# DummyLoad.net
KiCad netlist of a schematic drawn in EAGLE
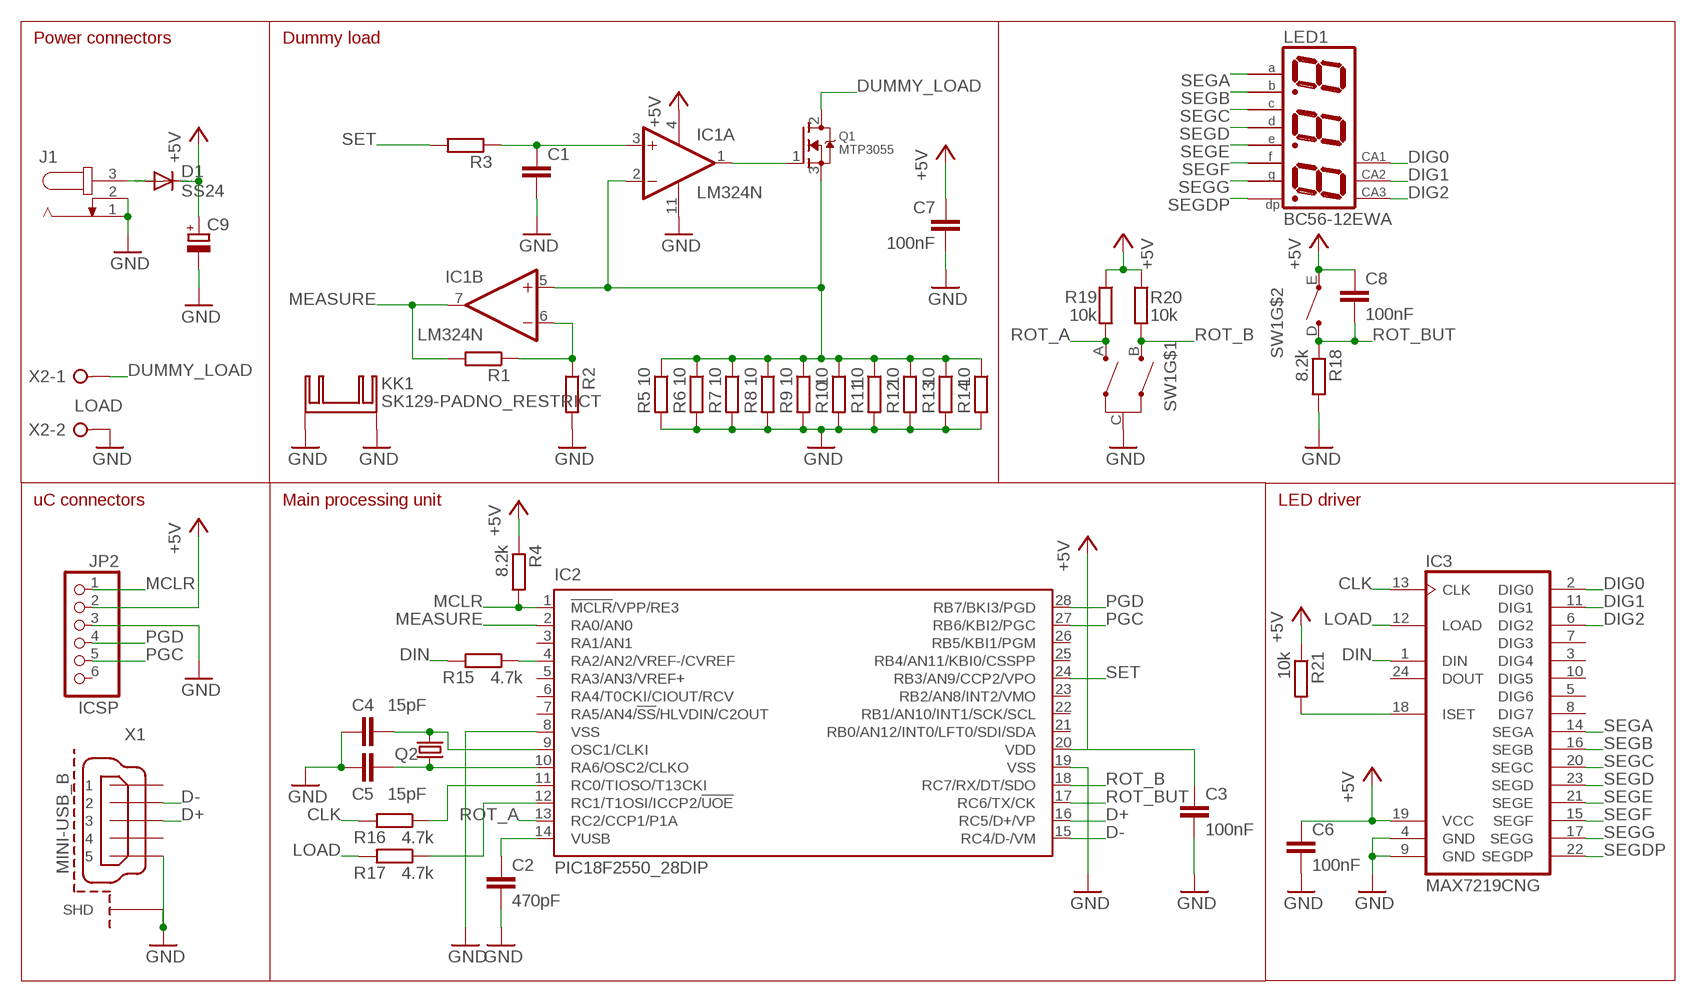
[diagram p0: schematic, sheet 1]

(export (version "E")
  (design (tool "Eeschema 10.0.6"))
  (components
    (comp (ref "C1")
      (value "C-EUC1206")
      (footprint "eagle-import:C1206")
      (libsource (lib "eagle-import") (part "C-EUC1206"))
    )
    (comp (ref "C2")
      (value "470pF")
      (footprint "eagle-import:C1206")
      (libsource (lib "eagle-import") (part "C-EUC1206"))
    )
    (comp (ref "C3")
      (value "100nF")
      (footprint "eagle-import:C1206")
      (libsource (lib "eagle-import") (part "C-EUC1206"))
    )
    (comp (ref "C4")
      (value "15pF")
      (footprint "eagle-import:C1206")
      (libsource (lib "eagle-import") (part "C-EUC1206"))
    )
    (comp (ref "C5")
      (value "15pF")
      (footprint "eagle-import:C1206")
      (libsource (lib "eagle-import") (part "C-EUC1206"))
    )
    (comp (ref "C6")
      (value "100nF")
      (footprint "eagle-import:C1206")
      (libsource (lib "eagle-import") (part "C-EUC1206"))
    )
    (comp (ref "C7")
      (value "100nF")
      (footprint "eagle-import:C1206")
      (libsource (lib "eagle-import") (part "C-EUC1206"))
    )
    (comp (ref "C8")
      (value "100nF")
      (footprint "eagle-import:C1206")
      (libsource (lib "eagle-import") (part "C-EUC1206"))
    )
    (comp (ref "C9")
      (value "CPOL-EUD/7343-31R")
      (footprint "eagle-import:D_7343-31R")
      (libsource (lib "eagle-import") (part "CPOL-EUD/7343-31R"))
    )
    (comp (ref "D1")
      (value "SS24")
      (footprint "eagle-import:DO214AA")
      (libsource (lib "eagle-import") (part "DIODE-DO214AA"))
    )
    (comp (ref "IC1")
      (value "LM324N")
      (footprint "eagle-import:DIL14")
      (libsource (lib "eagle-import") (part "LM324N"))
    )
    (comp (ref "IC2")
      (value "PIC18F2550_28DIP")
      (footprint "eagle-import:DIL28-3")
      (fields (field (name "MF") "MICROCHIP") (field (name "MPN") "PIC18F2550-I/SP"))
      (libsource (lib "eagle-import") (part "PIC18F2_28DIP550"))
    )
    (comp (ref "IC3")
      (value "MAX7219CNG")
      (footprint "eagle-import:DIL24-3")
      (fields (field (name "MF") "MAXIM"))
      (libsource (lib "eagle-import") (part "MAX7219CNG"))
    )
    (comp (ref "J1")
      (value "JACK-PLUG0")
      (footprint "eagle-import:SPC4077")
      (libsource (lib "eagle-import") (part "JACK-PLUG0"))
    )
    (comp (ref "JP2")
      (value "ICSP")
      (footprint "eagle-import:1X06_90")
      (libsource (lib "eagle-import") (part "PINHD-1X6/90"))
    )
    (comp (ref "KK1")
      (value "SK129-PADNO_RESTRICT")
      (footprint "eagle-import:SK129-NO_RESTRICT")
      (libsource (lib "eagle-import") (part "SK129-PADNO_RESTRICT"))
    )
    (comp (ref "LED1")
      (value "BC56-12EWA")
      (footprint "eagle-import:BX56-12")
      (libsource (lib "eagle-import") (part "B?56-12WACE"))
    )
    (comp (ref "Q1")
      (value "MTP3055")
      (footprint "eagle-import:TO220V")
      (libsource (lib "eagle-import") (part "MOSFET-NGDS_TO220V"))
    )
    (comp (ref "Q2")
      (value "CRYSTALHC49S")
      (footprint "eagle-import:HC49_S")
      (libsource (lib "eagle-import") (part "CRYSTALHC49S"))
    )
    (comp (ref "R1")
      (value "R-EU_R1206")
      (footprint "eagle-import:R1206")
      (libsource (lib "eagle-import") (part "R-EU_R1206"))
    )
    (comp (ref "R2")
      (value "R-EU_R1206")
      (footprint "eagle-import:R1206")
      (libsource (lib "eagle-import") (part "R-EU_R1206"))
    )
    (comp (ref "R3")
      (value "R-EU_R1206")
      (footprint "eagle-import:R1206")
      (libsource (lib "eagle-import") (part "R-EU_R1206"))
    )
    (comp (ref "R4")
      (value "8.2k")
      (footprint "eagle-import:R1206")
      (libsource (lib "eagle-import") (part "R-EU_R1206"))
    )
    (comp (ref "R5")
      (value "10")
      (footprint "eagle-import:0309_12")
      (libsource (lib "eagle-import") (part "R-EU_0309/12"))
    )
    (comp (ref "R6")
      (value "10")
      (footprint "eagle-import:0309_12")
      (libsource (lib "eagle-import") (part "R-EU_0309/12"))
    )
    (comp (ref "R7")
      (value "10")
      (footprint "eagle-import:0309_12")
      (libsource (lib "eagle-import") (part "R-EU_0309/12"))
    )
    (comp (ref "R8")
      (value "10")
      (footprint "eagle-import:0309_12")
      (libsource (lib "eagle-import") (part "R-EU_0309/12"))
    )
    (comp (ref "R9")
      (value "10")
      (footprint "eagle-import:0309_12")
      (libsource (lib "eagle-import") (part "R-EU_0309/12"))
    )
    (comp (ref "R10")
      (value "10")
      (footprint "eagle-import:0309_12")
      (libsource (lib "eagle-import") (part "R-EU_0309/12"))
    )
    (comp (ref "R11")
      (value "10")
      (footprint "eagle-import:0309_12")
      (libsource (lib "eagle-import") (part "R-EU_0309/12"))
    )
    (comp (ref "R12")
      (value "10")
      (footprint "eagle-import:0309_12")
      (libsource (lib "eagle-import") (part "R-EU_0309/12"))
    )
    (comp (ref "R13")
      (value "10")
      (footprint "eagle-import:0309_12")
      (libsource (lib "eagle-import") (part "R-EU_0309/12"))
    )
    (comp (ref "R14")
      (value "10")
      (footprint "eagle-import:0309_12")
      (libsource (lib "eagle-import") (part "R-EU_0309/12"))
    )
    (comp (ref "R15")
      (value "4.7k")
      (footprint "eagle-import:R1206")
      (libsource (lib "eagle-import") (part "R-EU_R1206"))
    )
    (comp (ref "R16")
      (value "4.7k")
      (footprint "eagle-import:R1206")
      (libsource (lib "eagle-import") (part "R-EU_R1206"))
    )
    (comp (ref "R17")
      (value "4.7k")
      (footprint "eagle-import:R1206")
      (libsource (lib "eagle-import") (part "R-EU_R1206"))
    )
    (comp (ref "R18")
      (value "8.2k")
      (footprint "eagle-import:R1206")
      (libsource (lib "eagle-import") (part "R-EU_R1206"))
    )
    (comp (ref "R19")
      (value "10k")
      (footprint "eagle-import:R1206")
      (libsource (lib "eagle-import") (part "R-EU_R1206"))
    )
    (comp (ref "R20")
      (value "10k")
      (footprint "eagle-import:R1206")
      (libsource (lib "eagle-import") (part "R-EU_R1206"))
    )
    (comp (ref "R21")
      (value "10k")
      (footprint "eagle-import:R1206")
      (libsource (lib "eagle-import") (part "R-EU_R1206"))
    )
    (comp (ref "SW1")
      (value "EC11B-V-T")
      (footprint "eagle-import:EC11B-V")
      (libsource (lib "eagle-import") (part "EC11B-V-T"))
    )
    (comp (ref "X1")
      (value "MINI-USB_B")
      (footprint "eagle-import:MINI-USB-B")
      (libsource (lib "eagle-import") (part "MINI-USB_B"))
    )
    (comp (ref "X2")
      (value "LOAD")
      (footprint "eagle-import:W237-132")
      (libsource (lib "eagle-import") (part "W237-02P"))
    )
  )
  (nets
    (net (code "1") (name "+5V") (class "Default")
      (node (ref "C3") (pin "1") (pinfunction "1_1") (pintype "passive"))
      (node (ref "C6") (pin "1") (pinfunction "1_1") (pintype "passive"))
      (node (ref "C7") (pin "1") (pinfunction "1_1") (pintype "passive"))
      (node (ref "C8") (pin "1") (pinfunction "1_1") (pintype "passive"))
      (node (ref "C9") (pin "+") (pinfunction "+_+") (pintype "passive"))
      (node (ref "D1") (pin "C") (pinfunction "C_C") (pintype "passive"))
      (node (ref "IC1") (pin "4") (pinfunction "V+_4") (pintype "power_in"))
      (node (ref "IC2") (pin "20") (pinfunction "VDD_20") (pintype "power_in"))
      (node (ref "IC3") (pin "19") (pinfunction "VCC_19") (pintype "power_in"))
      (node (ref "JP2") (pin "2") (pinfunction "2_2") (pintype "passive"))
      (node (ref "R19") (pin "1") (pinfunction "1_1") (pintype "passive"))
      (node (ref "R20") (pin "1") (pinfunction "1_1") (pintype "passive"))
      (node (ref "R21") (pin "1") (pinfunction "1_1") (pintype "passive"))
      (node (ref "R4") (pin "1") (pinfunction "1_1") (pintype "passive"))
      (node (ref "SW1") (pin "E") (pinfunction "E_E") (pintype "passive"))
    )
    (net (code "2") (name "/CLK") (class "Default")
      (node (ref "IC3") (pin "13") (pinfunction "CLK_13") (pintype "input"))
      (node (ref "R16") (pin "2") (pinfunction "2_2") (pintype "passive"))
    )
    (net (code "3") (name "/D+") (class "Default")
      (node (ref "IC2") (pin "16") (pinfunction "RC5/D+/VP_16") (pintype "bidirectional"))
      (node (ref "X1") (pin "3") (pinfunction "3_3") (pintype "passive"))
    )
    (net (code "4") (name "/D-") (class "Default")
      (node (ref "IC2") (pin "15") (pinfunction "RC4/D-/VM_15") (pintype "bidirectional"))
      (node (ref "X1") (pin "2") (pinfunction "2_2") (pintype "passive"))
    )
    (net (code "5") (name "/DIG0") (class "Default")
      (node (ref "IC3") (pin "2") (pinfunction "DIG0_2") (pintype "output"))
      (node (ref "LED1") (pin "12") (pinfunction "CA_12") (pintype "passive"))
    )
    (net (code "6") (name "/DIG1") (class "Default")
      (node (ref "IC3") (pin "11") (pinfunction "DIG1_11") (pintype "output"))
      (node (ref "LED1") (pin "9") (pinfunction "CA_9") (pintype "passive"))
    )
    (net (code "7") (name "/DIG2") (class "Default")
      (node (ref "IC3") (pin "6") (pinfunction "DIG2_6") (pintype "output"))
      (node (ref "LED1") (pin "8") (pinfunction "CA_8") (pintype "passive"))
    )
    (net (code "8") (name "/DIN") (class "Default")
      (node (ref "IC3") (pin "1") (pinfunction "DIN_1") (pintype "input"))
      (node (ref "R15") (pin "2") (pinfunction "2_2") (pintype "passive"))
    )
    (net (code "9") (name "/DUMMY_LOAD") (class "Default")
      (node (ref "Q1") (pin "2") (pinfunction "D_2") (pintype "bidirectional"))
      (node (ref "X2") (pin "1") (pinfunction "KL_1") (pintype "passive"))
    )
    (net (code "10") (name "/LOAD") (class "Default")
      (node (ref "IC3") (pin "12") (pinfunction "LOAD_12") (pintype "input"))
      (node (ref "R17") (pin "2") (pinfunction "2_2") (pintype "passive"))
    )
    (net (code "11") (name "/MCLR") (class "Default")
      (node (ref "IC2") (pin "1") (pinfunction "~{MCLR}/VPP/RE3_1") (pintype "input"))
      (node (ref "JP2") (pin "1") (pinfunction "1_1") (pintype "passive"))
      (node (ref "R4") (pin "2") (pinfunction "2_2") (pintype "passive"))
    )
    (net (code "12") (name "/MEASURE") (class "Default")
      (node (ref "IC1") (pin "7") (pinfunction "OUT_7") (pintype "output"))
      (node (ref "IC2") (pin "2") (pinfunction "RA0/AN0_2") (pintype "bidirectional"))
      (node (ref "R1") (pin "2") (pinfunction "2_2") (pintype "passive"))
    )
    (net (code "13") (name "/PGC") (class "Default")
      (node (ref "IC2") (pin "27") (pinfunction "RB6/KBI2/PGC_27") (pintype "bidirectional"))
      (node (ref "JP2") (pin "5") (pinfunction "5_5") (pintype "passive"))
    )
    (net (code "14") (name "/PGD") (class "Default")
      (node (ref "IC2") (pin "28") (pinfunction "RB7/BKI3/PGD_28") (pintype "bidirectional"))
      (node (ref "JP2") (pin "4") (pinfunction "4_4") (pintype "passive"))
    )
    (net (code "15") (name "/ROT_A") (class "Default")
      (node (ref "IC2") (pin "13") (pinfunction "RC2/CCP1/P1A_13") (pintype "bidirectional"))
      (node (ref "R19") (pin "2") (pinfunction "2_2") (pintype "passive"))
      (node (ref "SW1") (pin "A") (pinfunction "A_A") (pintype "passive"))
    )
    (net (code "16") (name "/ROT_B") (class "Default")
      (node (ref "IC2") (pin "18") (pinfunction "RC7/RX/DT/SDO_18") (pintype "bidirectional"))
      (node (ref "R20") (pin "2") (pinfunction "2_2") (pintype "passive"))
      (node (ref "SW1") (pin "B") (pinfunction "B_B") (pintype "passive"))
    )
    (net (code "17") (name "/ROT_BUT") (class "Default")
      (node (ref "C8") (pin "2") (pinfunction "2_2") (pintype "passive"))
      (node (ref "IC2") (pin "17") (pinfunction "RC6/TX/CK_17") (pintype "bidirectional"))
      (node (ref "R18") (pin "1") (pinfunction "1_1") (pintype "passive"))
      (node (ref "SW1") (pin "D") (pinfunction "D_D") (pintype "passive"))
    )
    (net (code "18") (name "/SEGA") (class "Default")
      (node (ref "IC3") (pin "14") (pinfunction "SEGA_14") (pintype "output"))
      (node (ref "LED1") (pin "11") (pinfunction "A_11") (pintype "passive"))
    )
    (net (code "19") (name "/SEGB") (class "Default")
      (node (ref "IC3") (pin "16") (pinfunction "SEGB_16") (pintype "output"))
      (node (ref "LED1") (pin "7") (pinfunction "B_7") (pintype "passive"))
    )
    (net (code "20") (name "/SEGC") (class "Default")
      (node (ref "IC3") (pin "20") (pinfunction "SEGC_20") (pintype "output"))
      (node (ref "LED1") (pin "4") (pinfunction "C_4") (pintype "passive"))
    )
    (net (code "21") (name "/SEGD") (class "Default")
      (node (ref "IC3") (pin "23") (pinfunction "SEGD_23") (pintype "output"))
      (node (ref "LED1") (pin "2") (pinfunction "D_2") (pintype "passive"))
    )
    (net (code "22") (name "/SEGDP") (class "Default")
      (node (ref "IC3") (pin "22") (pinfunction "SEGDP_22") (pintype "output"))
      (node (ref "LED1") (pin "3") (pinfunction "DP_3") (pintype "passive"))
    )
    (net (code "23") (name "/SEGE") (class "Default")
      (node (ref "IC3") (pin "21") (pinfunction "SEGE_21") (pintype "output"))
      (node (ref "LED1") (pin "1") (pinfunction "E_1") (pintype "passive"))
    )
    (net (code "24") (name "/SEGF") (class "Default")
      (node (ref "IC3") (pin "15") (pinfunction "SEGF_15") (pintype "output"))
      (node (ref "LED1") (pin "10") (pinfunction "F_10") (pintype "passive"))
    )
    (net (code "25") (name "/SEGG") (class "Default")
      (node (ref "IC3") (pin "17") (pinfunction "SEGG_17") (pintype "output"))
      (node (ref "LED1") (pin "5") (pinfunction "G_5") (pintype "passive"))
    )
    (net (code "26") (name "/SET") (class "Default")
      (node (ref "IC2") (pin "24") (pinfunction "RB3/AN9/CCP2/VPO_24") (pintype "bidirectional"))
      (node (ref "R3") (pin "2") (pinfunction "2_2") (pintype "passive"))
    )
    (net (code "27") (name "GND") (class "Default")
      (node (ref "C1") (pin "2") (pinfunction "2_2") (pintype "passive"))
      (node (ref "C2") (pin "2") (pinfunction "2_2") (pintype "passive"))
      (node (ref "C3") (pin "2") (pinfunction "2_2") (pintype "passive"))
      (node (ref "C4") (pin "1") (pinfunction "1_1") (pintype "passive"))
      (node (ref "C5") (pin "1") (pinfunction "1_1") (pintype "passive"))
      (node (ref "C6") (pin "2") (pinfunction "2_2") (pintype "passive"))
      (node (ref "C7") (pin "2") (pinfunction "2_2") (pintype "passive"))
      (node (ref "C9") (pin "-") (pinfunction "-_-") (pintype "passive"))
      (node (ref "IC1") (pin "11") (pinfunction "V-_11") (pintype "power_in"))
      (node (ref "IC2") (pin "19") (pinfunction "VSS_19") (pintype "power_in"))
      (node (ref "IC2") (pin "8") (pinfunction "VSS_8") (pintype "power_in"))
      (node (ref "IC3") (pin "4") (pinfunction "GND_4") (pintype "power_in"))
      (node (ref "IC3") (pin "9") (pinfunction "GND_9") (pintype "power_in"))
      (node (ref "J1") (pin "1") (pinfunction "1_1") (pintype "passive"))
      (node (ref "J1") (pin "2") (pinfunction "2_2") (pintype "passive"))
      (node (ref "JP2") (pin "3") (pinfunction "3_3") (pintype "passive"))
      (node (ref "KK1") (pin "A2,5") (pinfunction "K_A2,5") (pintype "passive"))
      (node (ref "KK1") (pin "B2,5") (pinfunction "K_B2,5") (pintype "passive"))
      (node (ref "R10") (pin "2") (pinfunction "2_2") (pintype "passive"))
      (node (ref "R11") (pin "2") (pinfunction "2_2") (pintype "passive"))
      (node (ref "R12") (pin "2") (pinfunction "2_2") (pintype "passive"))
      (node (ref "R13") (pin "2") (pinfunction "2_2") (pintype "passive"))
      (node (ref "R14") (pin "2") (pinfunction "2_2") (pintype "passive"))
      (node (ref "R18") (pin "2") (pinfunction "2_2") (pintype "passive"))
      (node (ref "R2") (pin "2") (pinfunction "2_2") (pintype "passive"))
      (node (ref "R5") (pin "2") (pinfunction "2_2") (pintype "passive"))
      (node (ref "R6") (pin "2") (pinfunction "2_2") (pintype "passive"))
      (node (ref "R7") (pin "2") (pinfunction "2_2") (pintype "passive"))
      (node (ref "R8") (pin "2") (pinfunction "2_2") (pintype "passive"))
      (node (ref "R9") (pin "2") (pinfunction "2_2") (pintype "passive"))
      (node (ref "SW1") (pin "C") (pinfunction "C_C") (pintype "passive"))
      (node (ref "X1") (pin "5") (pinfunction "5_5") (pintype "passive"))
      (node (ref "X1") (pin "M1") (pinfunction "SHD_M1") (pintype "passive"))
      (node (ref "X1") (pin "M2") (pinfunction "SHD_M2") (pintype "passive"))
      (node (ref "X1") (pin "M3") (pinfunction "SHD_M3") (pintype "passive"))
      (node (ref "X1") (pin "M4") (pinfunction "SHD_M4") (pintype "passive"))
      (node (ref "X2") (pin "2") (pinfunction "KL_2") (pintype "passive"))
    )
    (net (code "28") (name "Net-(D1-PadA)") (class "Default")
      (node (ref "D1") (pin "A") (pinfunction "A_A") (pintype "passive"))
      (node (ref "J1") (pin "3") (pinfunction "3_3") (pintype "passive"))
    )
    (net (code "29") (name "Net-(IC1A-+IN)") (class "Default")
      (node (ref "C1") (pin "1") (pinfunction "1_1") (pintype "passive"))
      (node (ref "IC1") (pin "3") (pinfunction "+IN_3") (pintype "input"))
      (node (ref "R3") (pin "1") (pinfunction "1_1") (pintype "passive"))
    )
    (net (code "30") (name "Net-(IC1A--IN)") (class "Default")
      (node (ref "IC1") (pin "2") (pinfunction "-IN_2") (pintype "input"))
      (node (ref "IC1") (pin "5") (pinfunction "+IN_5") (pintype "input"))
      (node (ref "Q1") (pin "3") (pinfunction "S_3") (pintype "bidirectional"))
      (node (ref "R10") (pin "1") (pinfunction "1_1") (pintype "passive"))
      (node (ref "R11") (pin "1") (pinfunction "1_1") (pintype "passive"))
      (node (ref "R12") (pin "1") (pinfunction "1_1") (pintype "passive"))
      (node (ref "R13") (pin "1") (pinfunction "1_1") (pintype "passive"))
      (node (ref "R14") (pin "1") (pinfunction "1_1") (pintype "passive"))
      (node (ref "R5") (pin "1") (pinfunction "1_1") (pintype "passive"))
      (node (ref "R6") (pin "1") (pinfunction "1_1") (pintype "passive"))
      (node (ref "R7") (pin "1") (pinfunction "1_1") (pintype "passive"))
      (node (ref "R8") (pin "1") (pinfunction "1_1") (pintype "passive"))
      (node (ref "R9") (pin "1") (pinfunction "1_1") (pintype "passive"))
    )
    (net (code "31") (name "Net-(IC1A-OUT)") (class "Default")
      (node (ref "IC1") (pin "1") (pinfunction "OUT_1") (pintype "output"))
      (node (ref "Q1") (pin "1") (pinfunction "G_1") (pintype "bidirectional"))
    )
    (net (code "32") (name "Net-(IC1B--IN)") (class "Default")
      (node (ref "IC1") (pin "6") (pinfunction "-IN_6") (pintype "input"))
      (node (ref "R1") (pin "1") (pinfunction "1_1") (pintype "passive"))
      (node (ref "R2") (pin "1") (pinfunction "1_1") (pintype "passive"))
    )
    (net (code "33") (name "Net-(IC2-OSC1{slash}CLKI)") (class "Default")
      (node (ref "C4") (pin "2") (pinfunction "2_2") (pintype "passive"))
      (node (ref "IC2") (pin "9") (pinfunction "OSC1/CLKI_9") (pintype "input"))
      (node (ref "Q2") (pin "2") (pinfunction "2_2") (pintype "passive"))
    )
    (net (code "34") (name "Net-(IC2-RA2{slash}AN2{slash}VREF-{slash}CVREF)") (class "Default")
      (node (ref "IC2") (pin "4") (pinfunction "RA2/AN2/VREF-/CVREF_4") (pintype "bidirectional"))
      (node (ref "R15") (pin "1") (pinfunction "1_1") (pintype "passive"))
    )
    (net (code "35") (name "Net-(IC2-RA6{slash}OSC2{slash}CLKO)") (class "Default")
      (node (ref "C5") (pin "2") (pinfunction "2_2") (pintype "passive"))
      (node (ref "IC2") (pin "10") (pinfunction "RA6/OSC2/CLKO_10") (pintype "output"))
      (node (ref "Q2") (pin "1") (pinfunction "1_1") (pintype "passive"))
    )
    (net (code "36") (name "Net-(IC2-RC0{slash}TIOSO{slash}T13CKI)") (class "Default")
      (node (ref "IC2") (pin "11") (pinfunction "RC0/TIOSO/T13CKI_11") (pintype "bidirectional"))
      (node (ref "R16") (pin "1") (pinfunction "1_1") (pintype "passive"))
    )
    (net (code "37") (name "Net-(IC2-RC1{slash}T1OSI{slash}ICCP2{slash}~{UOE})") (class "Default")
      (node (ref "IC2") (pin "12") (pinfunction "RC1/T1OSI/ICCP2/~{UOE}_12") (pintype "bidirectional"))
      (node (ref "R17") (pin "1") (pinfunction "1_1") (pintype "passive"))
    )
    (net (code "38") (name "Net-(IC2-VUSB)") (class "Default")
      (node (ref "C2") (pin "1") (pinfunction "1_1") (pintype "passive"))
      (node (ref "IC2") (pin "14") (pinfunction "VUSB_14") (pintype "bidirectional"))
    )
    (net (code "39") (name "Net-(IC3-ISET)") (class "Default")
      (node (ref "IC3") (pin "18") (pinfunction "ISET_18") (pintype "input"))
      (node (ref "R21") (pin "2") (pinfunction "2_2") (pintype "passive"))
    )
    (net (code "40") (name "unconnected-(IC2-RA1{slash}AN1-Pad3)") (class "Default")
      (node (ref "IC2") (pin "3") (pinfunction "RA1/AN1_3") (pintype "bidirectional"))
    )
    (net (code "41") (name "unconnected-(IC2-RA3{slash}AN3{slash}VREF+-Pad5)") (class "Default")
      (node (ref "IC2") (pin "5") (pinfunction "RA3/AN3/VREF+_5") (pintype "bidirectional"))
    )
    (net (code "42") (name "unconnected-(IC2-RA4{slash}T0CKI{slash}CIOUT{slash}RCV-Pad6)") (class "Default")
      (node (ref "IC2") (pin "6") (pinfunction "RA4/T0CKI/CIOUT/RCV_6") (pintype "bidirectional"))
    )
    (net (code "43") (name "unconnected-(IC2-RA5{slash}AN4{slash}~{SS}{slash}HLVDIN{slash}C2OUT-Pad7)") (class "Default")
      (node (ref "IC2") (pin "7") (pinfunction "RA5/AN4/~{SS}/HLVDIN/C2OUT_7") (pintype "bidirectional"))
    )
    (net (code "44") (name "unconnected-(IC2-RB0{slash}AN12{slash}INT0{slash}LFT0{slash}SDI{slash}SDA-Pad21)") (class "Default")
      (node (ref "IC2") (pin "21") (pinfunction "RB0/AN12/INT0/LFT0/SDI/SDA_21") (pintype "bidirectional"))
    )
    (net (code "45") (name "unconnected-(IC2-RB1{slash}AN10{slash}INT1{slash}SCK{slash}SCL-Pad22)") (class "Default")
      (node (ref "IC2") (pin "22") (pinfunction "RB1/AN10/INT1/SCK/SCL_22") (pintype "bidirectional"))
    )
    (net (code "46") (name "unconnected-(IC2-RB2{slash}AN8{slash}INT2{slash}VMO-Pad23)") (class "Default")
      (node (ref "IC2") (pin "23") (pinfunction "RB2/AN8/INT2/VMO_23") (pintype "bidirectional"))
    )
    (net (code "47") (name "unconnected-(IC2-RB4{slash}AN11{slash}KBI0{slash}CSSPP-Pad25)") (class "Default")
      (node (ref "IC2") (pin "25") (pinfunction "RB4/AN11/KBI0/CSSPP_25") (pintype "bidirectional"))
    )
    (net (code "48") (name "unconnected-(IC2-RB5{slash}KBI1{slash}PGM-Pad26)") (class "Default")
      (node (ref "IC2") (pin "26") (pinfunction "RB5/KBI1/PGM_26") (pintype "bidirectional"))
    )
    (net (code "49") (name "unconnected-(IC3-DIG3-Pad7)") (class "Default")
      (node (ref "IC3") (pin "7") (pinfunction "DIG3_7") (pintype "output"))
    )
    (net (code "50") (name "unconnected-(IC3-DIG4-Pad3)") (class "Default")
      (node (ref "IC3") (pin "3") (pinfunction "DIG4_3") (pintype "output"))
    )
    (net (code "51") (name "unconnected-(IC3-DIG5-Pad10)") (class "Default")
      (node (ref "IC3") (pin "10") (pinfunction "DIG5_10") (pintype "output"))
    )
    (net (code "52") (name "unconnected-(IC3-DIG6-Pad5)") (class "Default")
      (node (ref "IC3") (pin "5") (pinfunction "DIG6_5") (pintype "output"))
    )
    (net (code "53") (name "unconnected-(IC3-DIG7-Pad8)") (class "Default")
      (node (ref "IC3") (pin "8") (pinfunction "DIG7_8") (pintype "output"))
    )
    (net (code "54") (name "unconnected-(IC3-DOUT-Pad24)") (class "Default")
      (node (ref "IC3") (pin "24") (pinfunction "DOUT_24") (pintype "output"))
    )
    (net (code "55") (name "unconnected-(JP2-Pad6)") (class "Default")
      (node (ref "JP2") (pin "6") (pinfunction "6_6") (pintype "passive"))
    )
    (net (code "56") (name "unconnected-(X1-Pad1)") (class "Default")
      (node (ref "X1") (pin "1") (pinfunction "1_1") (pintype "passive"))
    )
    (net (code "57") (name "unconnected-(X1-Pad4)") (class "Default")
      (node (ref "X1") (pin "4") (pinfunction "4_4") (pintype "passive"))
    )
  )
)
